# 9-Safety-Relay-Schematic.net
KiCad netlist of a schematic drawn in Altium Designer
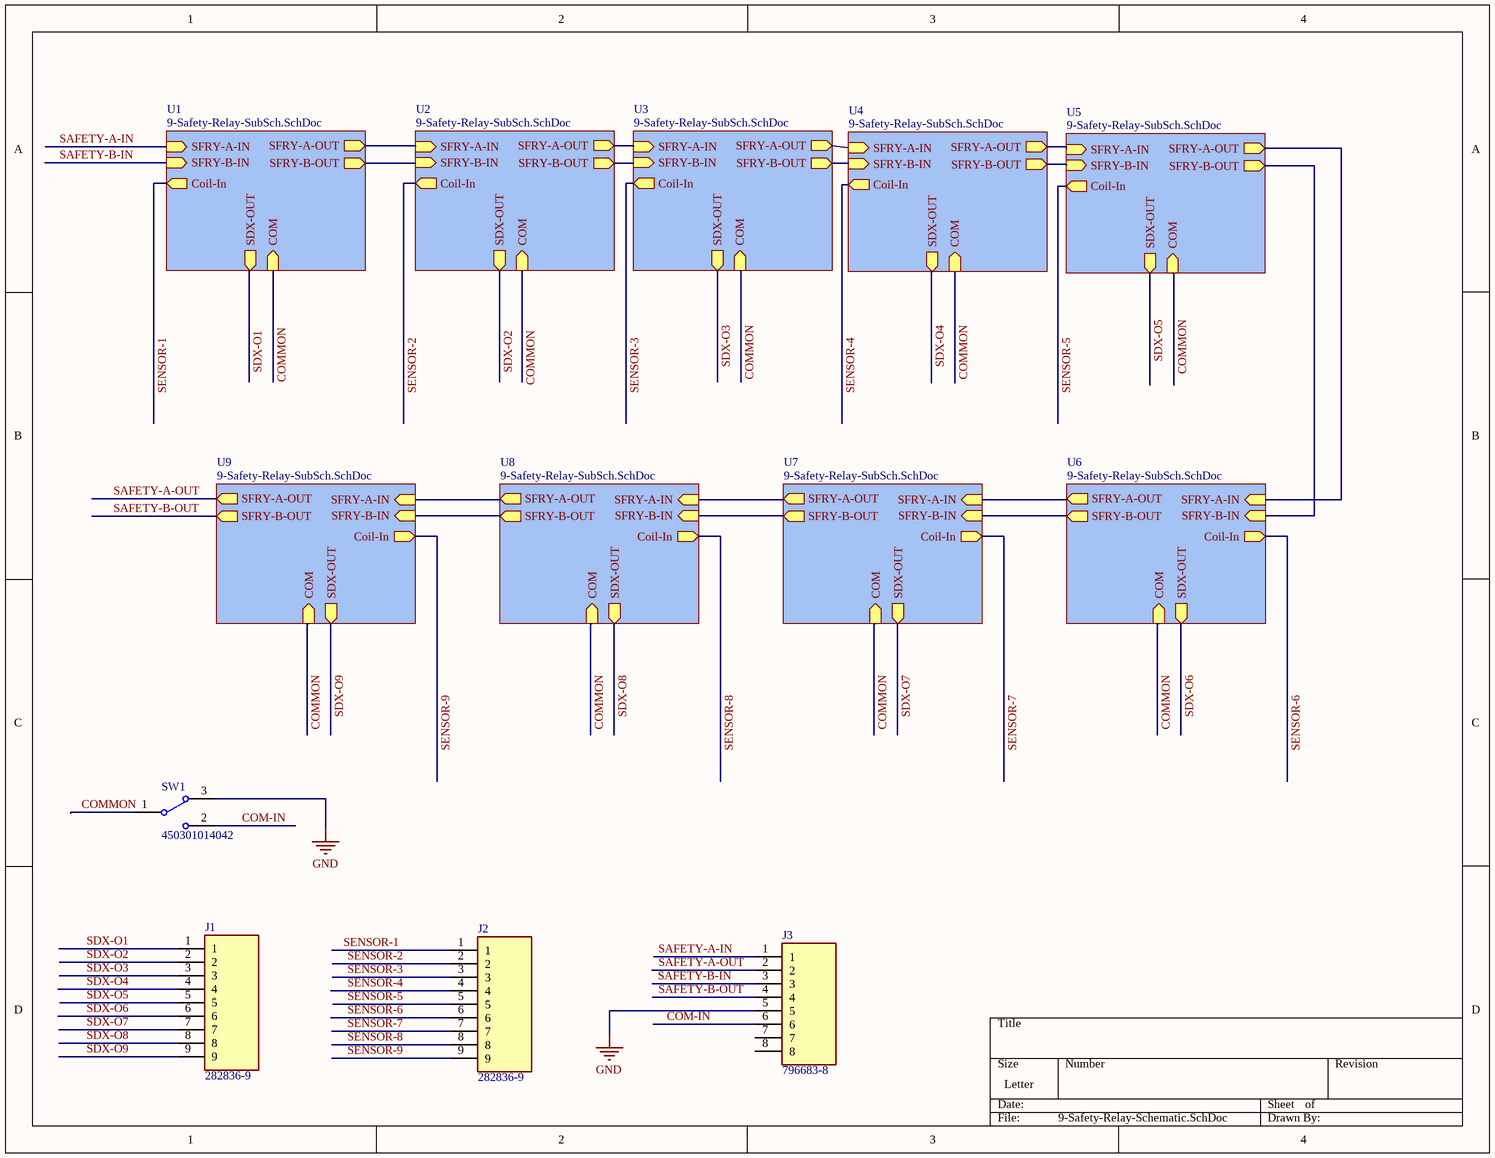
[diagram p0: 9-Safety-Relay-Schematic.SchDoc]

(export (version "E")
  (design (tool "Eeschema 10.0.6"))
  (components
    (comp (ref "J1")
      (value "282836-9")
      (footprint "SamacSys:SHDR9W130P0X500_1X9_4500X820X1020P")
      (description "Connector")
      (fields (field (name "MOUSER PART NUMBER") "571-282836-9") (field (name "RS PART NUMBER") "3617746"))
      (libsource (lib "*") (part "282836-9"))
    )
    (comp (ref "J2")
      (value "282836-9")
      (footprint "SamacSys:SHDR9W130P0X500_1X9_4500X820X1020P")
      (description "Connector")
      (fields (field (name "MOUSER PART NUMBER") "571-282836-9") (field (name "RS PART NUMBER") "3617746"))
      (libsource (lib "*") (part "282836-9"))
    )
    (comp (ref "J3")
      (value "796683-8")
      (footprint "SamacSys:SHDR8W110P0X500_1X8_4000X900X1520P")
      (description "Connector")
      (fields (field (name "MOUSER PART NUMBER") "571-796683-8"))
      (libsource (lib "*") (part "796683-8"))
    )
    (comp (ref "SW1")
      (value "450301014042")
      (footprint "450301014042")
      (description "WS-SLTV 10mm*2.5mm, SPDT, ON-ON, 2.54mm, straight type, THT, Mini Slide Switch, 3 pins")
      (fields (field (name "MANUFACTURER") "Wuerth Elektronik"))
      (libsource (lib "Altium Content Vault") (part "WE-SLIDE-SW-3"))
    )
  )
  (nets
    (net (code "1") (name "/COM-IN") (class "Default")
      (node (ref "J3") (pin "6") (pinfunction "6_6") (pintype "passive"))
      (node (ref "SW1") (pin "2") (pinfunction "2_2") (pintype "passive"))
    )
    (net (code "2") (name "/COMMON") (class "Default")
      (node (ref "SW1") (pin "1") (pinfunction "1_1") (pintype "passive"))
    )
    (net (code "3") (name "/SAFETY-A-IN") (class "Default")
      (node (ref "J3") (pin "1") (pinfunction "1_1") (pintype "passive"))
    )
    (net (code "4") (name "/SAFETY-A-OUT") (class "Default")
      (node (ref "J3") (pin "2") (pinfunction "2_2") (pintype "passive"))
    )
    (net (code "5") (name "/SAFETY-B-IN") (class "Default")
      (node (ref "J3") (pin "3") (pinfunction "3_3") (pintype "passive"))
    )
    (net (code "6") (name "/SAFETY-B-OUT") (class "Default")
      (node (ref "J3") (pin "4") (pinfunction "4_4") (pintype "passive"))
    )
    (net (code "7") (name "/SDX-O1") (class "Default")
      (node (ref "J1") (pin "1") (pinfunction "1_1") (pintype "passive"))
    )
    (net (code "8") (name "/SDX-O2") (class "Default")
      (node (ref "J1") (pin "2") (pinfunction "2_2") (pintype "passive"))
    )
    (net (code "9") (name "/SDX-O3") (class "Default")
      (node (ref "J1") (pin "3") (pinfunction "3_3") (pintype "passive"))
    )
    (net (code "10") (name "/SDX-O4") (class "Default")
      (node (ref "J1") (pin "4") (pinfunction "4_4") (pintype "passive"))
    )
    (net (code "11") (name "/SDX-O5") (class "Default")
      (node (ref "J1") (pin "5") (pinfunction "5_5") (pintype "passive"))
    )
    (net (code "12") (name "/SDX-O6") (class "Default")
      (node (ref "J1") (pin "6") (pinfunction "6_6") (pintype "passive"))
    )
    (net (code "13") (name "/SDX-O7") (class "Default")
      (node (ref "J1") (pin "7") (pinfunction "7_7") (pintype "passive"))
    )
    (net (code "14") (name "/SDX-O8") (class "Default")
      (node (ref "J1") (pin "8") (pinfunction "8_8") (pintype "passive"))
    )
    (net (code "15") (name "/SDX-O9") (class "Default")
      (node (ref "J1") (pin "9") (pinfunction "9_9") (pintype "passive"))
    )
    (net (code "16") (name "/SENSOR-1") (class "Default")
      (node (ref "J2") (pin "1") (pinfunction "1_1") (pintype "passive"))
    )
    (net (code "17") (name "/SENSOR-2") (class "Default")
      (node (ref "J2") (pin "2") (pinfunction "2_2") (pintype "passive"))
    )
    (net (code "18") (name "/SENSOR-3") (class "Default")
      (node (ref "J2") (pin "3") (pinfunction "3_3") (pintype "passive"))
    )
    (net (code "19") (name "/SENSOR-4") (class "Default")
      (node (ref "J2") (pin "4") (pinfunction "4_4") (pintype "passive"))
    )
    (net (code "20") (name "/SENSOR-5") (class "Default")
      (node (ref "J2") (pin "5") (pinfunction "5_5") (pintype "passive"))
    )
    (net (code "21") (name "/SENSOR-6") (class "Default")
      (node (ref "J2") (pin "6") (pinfunction "6_6") (pintype "passive"))
    )
    (net (code "22") (name "/SENSOR-7") (class "Default")
      (node (ref "J2") (pin "7") (pinfunction "7_7") (pintype "passive"))
    )
    (net (code "23") (name "/SENSOR-8") (class "Default")
      (node (ref "J2") (pin "8") (pinfunction "8_8") (pintype "passive"))
    )
    (net (code "24") (name "/SENSOR-9") (class "Default")
      (node (ref "J2") (pin "9") (pinfunction "9_9") (pintype "passive"))
    )
    (net (code "41") (name "GND") (class "Default")
      (node (ref "J3") (pin "5") (pinfunction "5_5") (pintype "passive"))
      (node (ref "SW1") (pin "3") (pinfunction "3_3") (pintype "passive"))
    )
    (net (code "42") (name "unconnected-(J3-Pad7)") (class "Default")
      (node (ref "J3") (pin "7") (pinfunction "7_7") (pintype "passive"))
    )
    (net (code "43") (name "unconnected-(J3-Pad8)") (class "Default")
      (node (ref "J3") (pin "8") (pinfunction "8_8") (pintype "passive"))
    )
  )
)
